# x16-to-mxm3.net
KiCad netlist of a schematic drawn in EAGLE
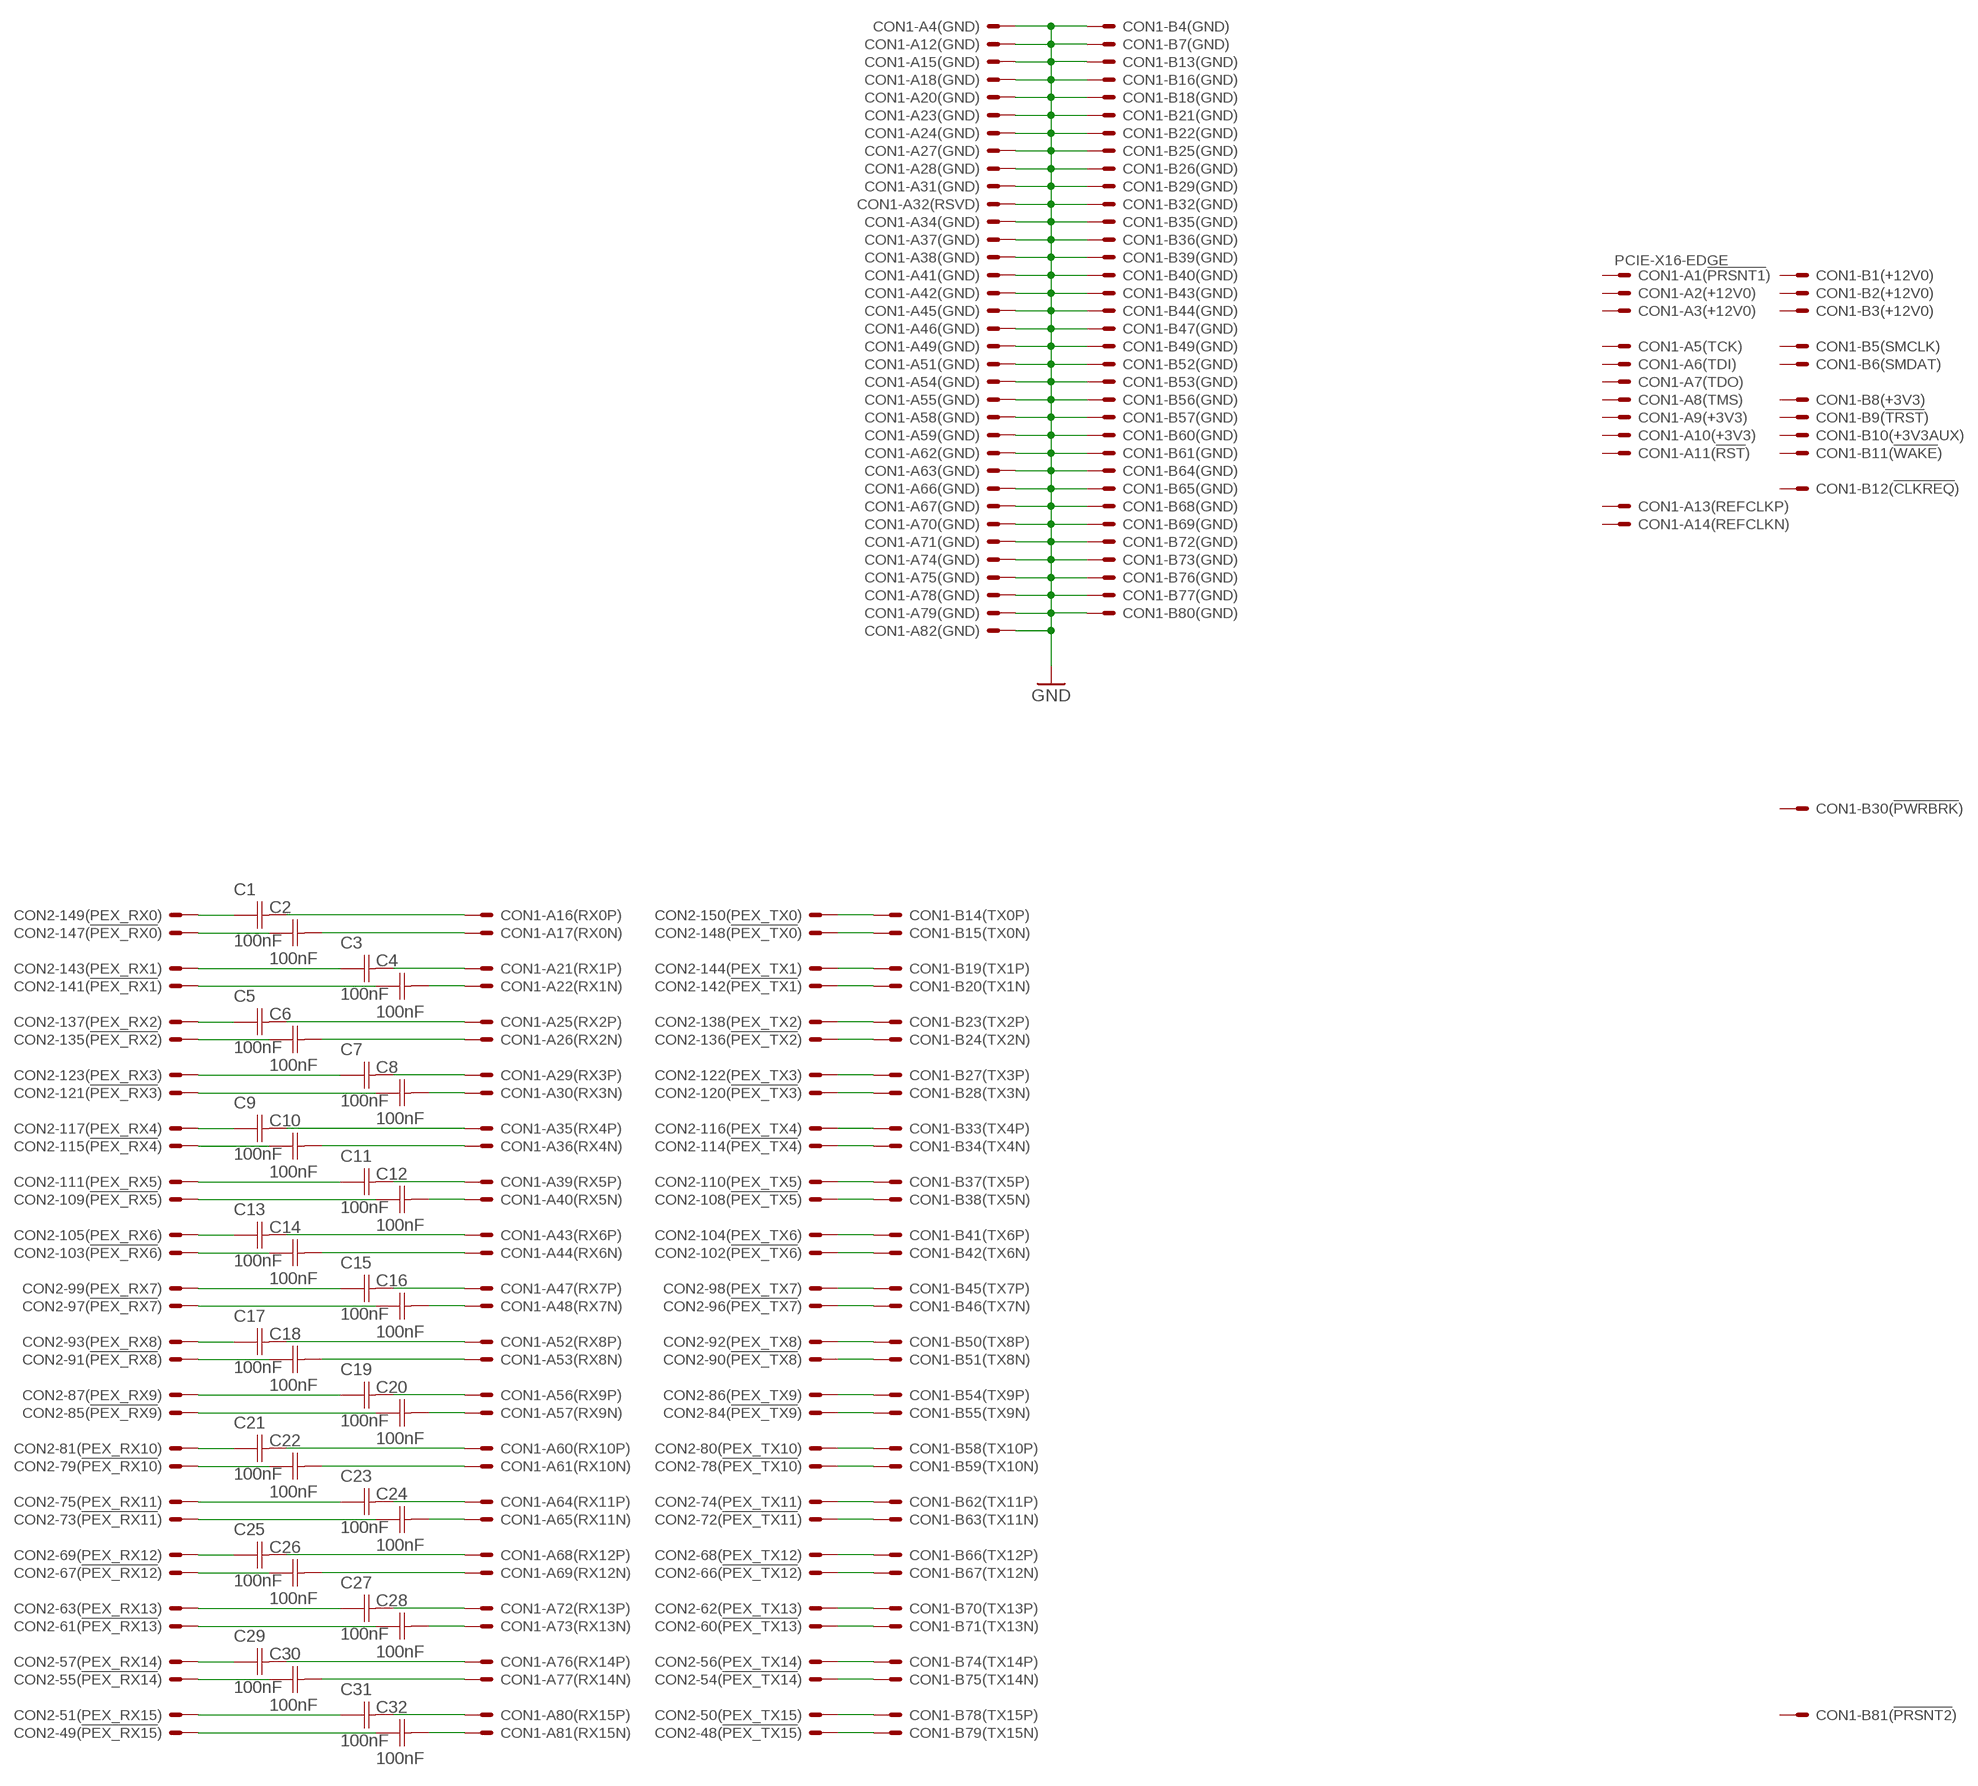
[diagram p0: schematic, sheet 1, part 1 of 2]
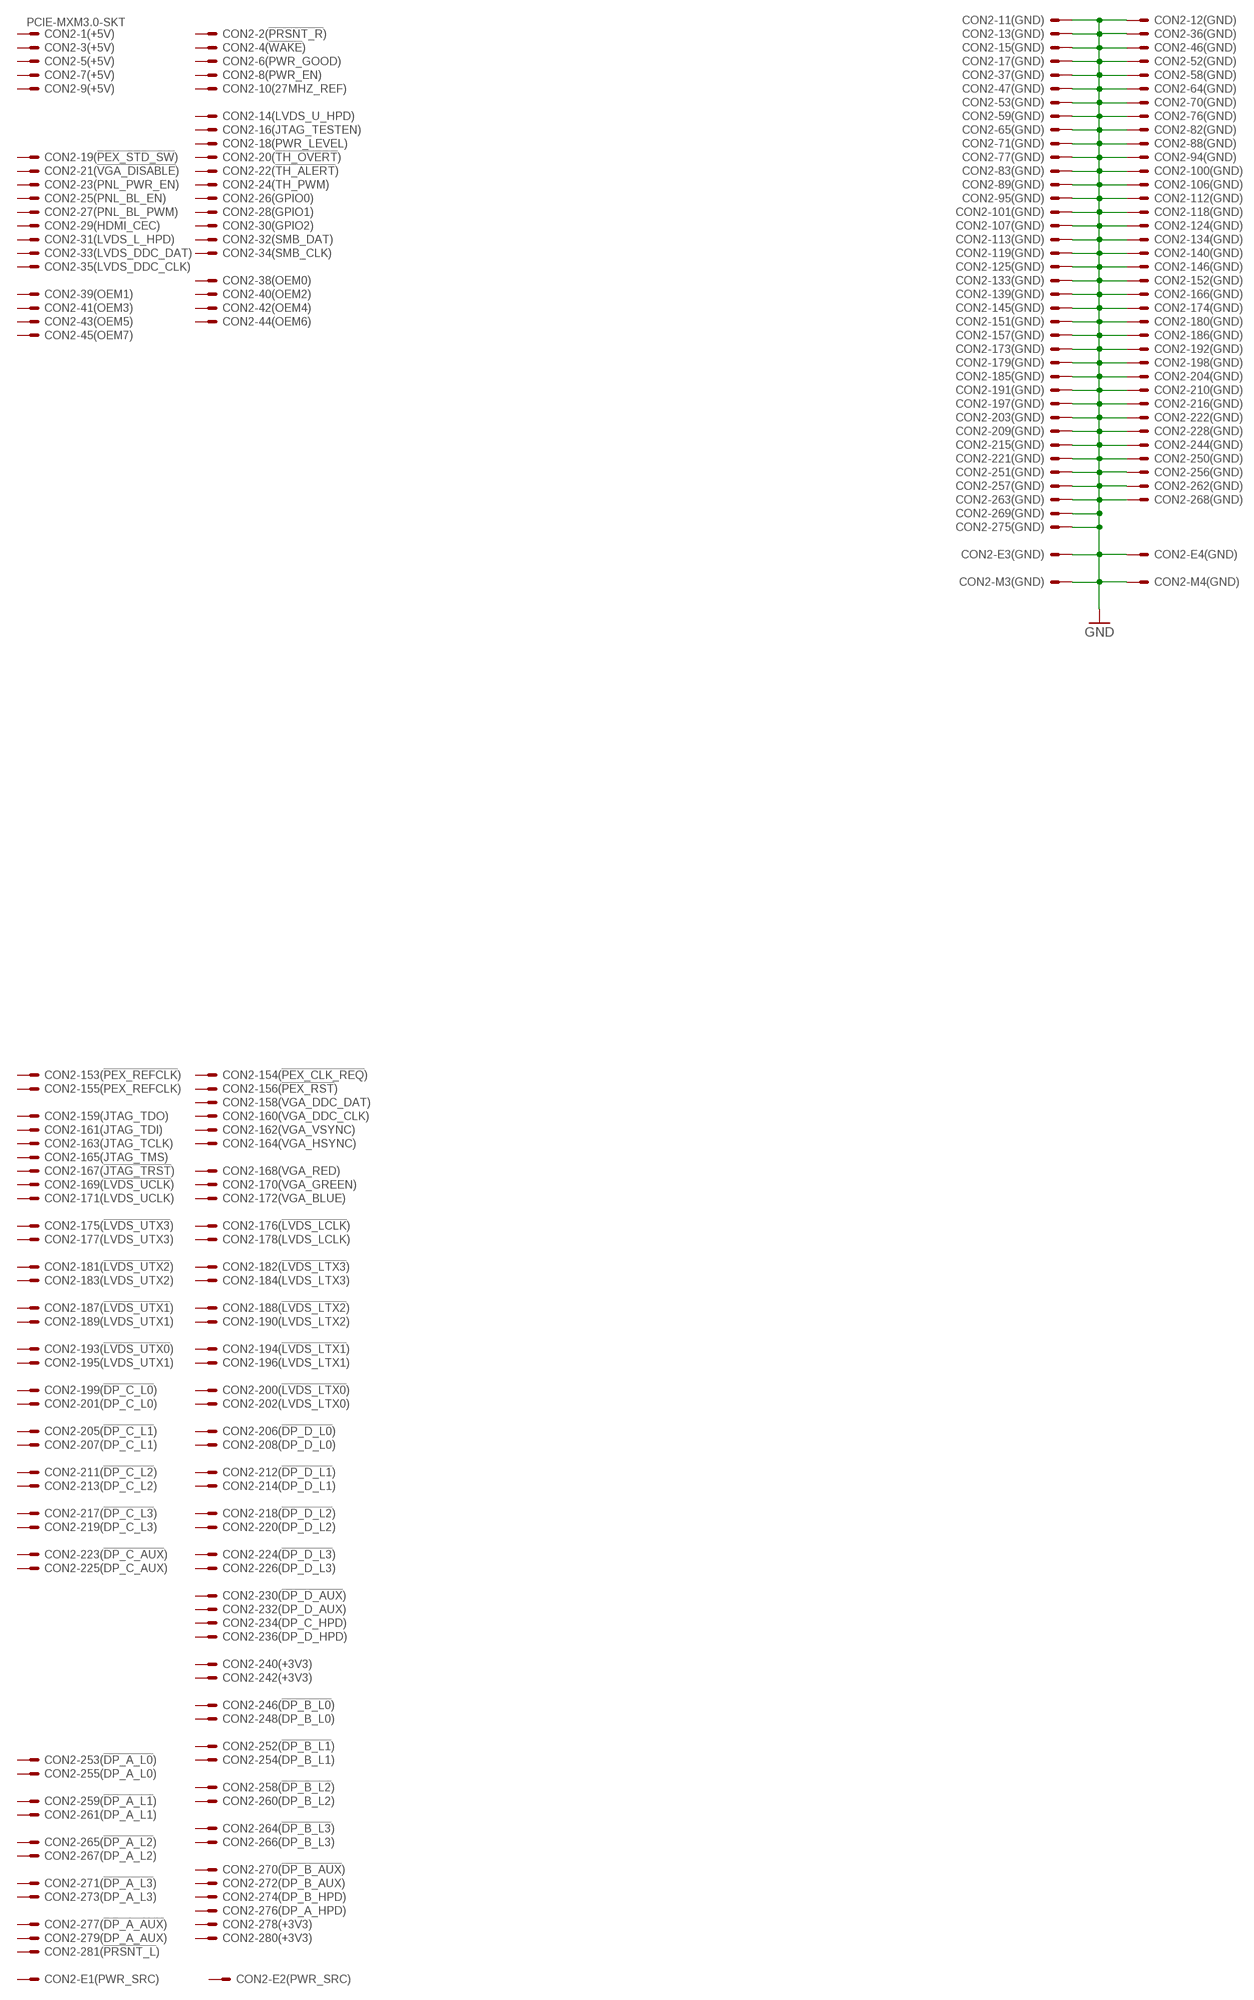
[diagram p1: schematic, sheet 1, part 2 of 2]

(export (version "E")
  (design (tool "Eeschema 10.0.6"))
  (components
    (comp (ref "C1")
      (value "100nF")
      (footprint "eagle-import:CAP0402")
      (libsource (lib "eagle-import") (part "CAPACITOR-0402"))
    )
    (comp (ref "C2")
      (value "100nF")
      (footprint "eagle-import:CAP0402")
      (libsource (lib "eagle-import") (part "CAPACITOR-0402"))
    )
    (comp (ref "C3")
      (value "100nF")
      (footprint "eagle-import:CAP0402")
      (libsource (lib "eagle-import") (part "CAPACITOR-0402"))
    )
    (comp (ref "C4")
      (value "100nF")
      (footprint "eagle-import:CAP0402")
      (libsource (lib "eagle-import") (part "CAPACITOR-0402"))
    )
    (comp (ref "C5")
      (value "100nF")
      (footprint "eagle-import:CAP0402")
      (libsource (lib "eagle-import") (part "CAPACITOR-0402"))
    )
    (comp (ref "C6")
      (value "100nF")
      (footprint "eagle-import:CAP0402")
      (libsource (lib "eagle-import") (part "CAPACITOR-0402"))
    )
    (comp (ref "C7")
      (value "100nF")
      (footprint "eagle-import:CAP0402")
      (libsource (lib "eagle-import") (part "CAPACITOR-0402"))
    )
    (comp (ref "C8")
      (value "100nF")
      (footprint "eagle-import:CAP0402")
      (libsource (lib "eagle-import") (part "CAPACITOR-0402"))
    )
    (comp (ref "C9")
      (value "100nF")
      (footprint "eagle-import:CAP0402")
      (libsource (lib "eagle-import") (part "CAPACITOR-0402"))
    )
    (comp (ref "C10")
      (value "100nF")
      (footprint "eagle-import:CAP0402")
      (libsource (lib "eagle-import") (part "CAPACITOR-0402"))
    )
    (comp (ref "C11")
      (value "100nF")
      (footprint "eagle-import:CAP0402")
      (libsource (lib "eagle-import") (part "CAPACITOR-0402"))
    )
    (comp (ref "C12")
      (value "100nF")
      (footprint "eagle-import:CAP0402")
      (libsource (lib "eagle-import") (part "CAPACITOR-0402"))
    )
    (comp (ref "C13")
      (value "100nF")
      (footprint "eagle-import:CAP0402")
      (libsource (lib "eagle-import") (part "CAPACITOR-0402"))
    )
    (comp (ref "C14")
      (value "100nF")
      (footprint "eagle-import:CAP0402")
      (libsource (lib "eagle-import") (part "CAPACITOR-0402"))
    )
    (comp (ref "C15")
      (value "100nF")
      (footprint "eagle-import:CAP0402")
      (libsource (lib "eagle-import") (part "CAPACITOR-0402"))
    )
    (comp (ref "C16")
      (value "100nF")
      (footprint "eagle-import:CAP0402")
      (libsource (lib "eagle-import") (part "CAPACITOR-0402"))
    )
    (comp (ref "C17")
      (value "100nF")
      (footprint "eagle-import:CAP0402")
      (libsource (lib "eagle-import") (part "CAPACITOR-0402"))
    )
    (comp (ref "C18")
      (value "100nF")
      (footprint "eagle-import:CAP0402")
      (libsource (lib "eagle-import") (part "CAPACITOR-0402"))
    )
    (comp (ref "C19")
      (value "100nF")
      (footprint "eagle-import:CAP0402")
      (libsource (lib "eagle-import") (part "CAPACITOR-0402"))
    )
    (comp (ref "C20")
      (value "100nF")
      (footprint "eagle-import:CAP0402")
      (libsource (lib "eagle-import") (part "CAPACITOR-0402"))
    )
    (comp (ref "C21")
      (value "100nF")
      (footprint "eagle-import:CAP0402")
      (libsource (lib "eagle-import") (part "CAPACITOR-0402"))
    )
    (comp (ref "C22")
      (value "100nF")
      (footprint "eagle-import:CAP0402")
      (libsource (lib "eagle-import") (part "CAPACITOR-0402"))
    )
    (comp (ref "C23")
      (value "100nF")
      (footprint "eagle-import:CAP0402")
      (libsource (lib "eagle-import") (part "CAPACITOR-0402"))
    )
    (comp (ref "C24")
      (value "100nF")
      (footprint "eagle-import:CAP0402")
      (libsource (lib "eagle-import") (part "CAPACITOR-0402"))
    )
    (comp (ref "C25")
      (value "100nF")
      (footprint "eagle-import:CAP0402")
      (libsource (lib "eagle-import") (part "CAPACITOR-0402"))
    )
    (comp (ref "C26")
      (value "100nF")
      (footprint "eagle-import:CAP0402")
      (libsource (lib "eagle-import") (part "CAPACITOR-0402"))
    )
    (comp (ref "C27")
      (value "100nF")
      (footprint "eagle-import:CAP0402")
      (libsource (lib "eagle-import") (part "CAPACITOR-0402"))
    )
    (comp (ref "C28")
      (value "100nF")
      (footprint "eagle-import:CAP0402")
      (libsource (lib "eagle-import") (part "CAPACITOR-0402"))
    )
    (comp (ref "C29")
      (value "100nF")
      (footprint "eagle-import:CAP0402")
      (libsource (lib "eagle-import") (part "CAPACITOR-0402"))
    )
    (comp (ref "C30")
      (value "100nF")
      (footprint "eagle-import:CAP0402")
      (libsource (lib "eagle-import") (part "CAPACITOR-0402"))
    )
    (comp (ref "C31")
      (value "100nF")
      (footprint "eagle-import:CAP0402")
      (libsource (lib "eagle-import") (part "CAPACITOR-0402"))
    )
    (comp (ref "C32")
      (value "100nF")
      (footprint "eagle-import:CAP0402")
      (libsource (lib "eagle-import") (part "CAPACITOR-0402"))
    )
    (comp (ref "CON1")
      (value "PCIE-X16-EDGE")
      (footprint "eagle-import:PCIE-X16-EDGE")
      (libsource (lib "eagle-import") (part "PCIE-X16-EDGE"))
    )
    (comp (ref "CON2")
      (value "PCIE-MXM3.0-SKT")
      (footprint "eagle-import:PCIE-MXM3.0-SKT")
      (libsource (lib "eagle-import") (part "PCIE-MXM3.0-SKT"))
    )
  )
  (nets
    (net (code "1") (name "GND") (class "Default")
      (node (ref "CON1") (pin "A12") (pinfunction "S_A12") (pintype "passive"))
      (node (ref "CON1") (pin "A15") (pinfunction "S_A15") (pintype "passive"))
      (node (ref "CON1") (pin "A18") (pinfunction "S_A18") (pintype "passive"))
      (node (ref "CON1") (pin "A20") (pinfunction "S_A20") (pintype "passive"))
      (node (ref "CON1") (pin "A23") (pinfunction "S_A23") (pintype "passive"))
      (node (ref "CON1") (pin "A24") (pinfunction "S_A24") (pintype "passive"))
      (node (ref "CON1") (pin "A27") (pinfunction "S_A27") (pintype "passive"))
      (node (ref "CON1") (pin "A28") (pinfunction "S_A28") (pintype "passive"))
      (node (ref "CON1") (pin "A31") (pinfunction "S_A31") (pintype "passive"))
      (node (ref "CON1") (pin "A32") (pinfunction "S_A32") (pintype "passive"))
      (node (ref "CON1") (pin "A34") (pinfunction "S_A34") (pintype "passive"))
      (node (ref "CON1") (pin "A37") (pinfunction "S_A37") (pintype "passive"))
      (node (ref "CON1") (pin "A38") (pinfunction "S_A38") (pintype "passive"))
      (node (ref "CON1") (pin "A4") (pinfunction "S_A4") (pintype "passive"))
      (node (ref "CON1") (pin "A41") (pinfunction "S_A41") (pintype "passive"))
      (node (ref "CON1") (pin "A42") (pinfunction "S_A42") (pintype "passive"))
      (node (ref "CON1") (pin "A45") (pinfunction "S_A45") (pintype "passive"))
      (node (ref "CON1") (pin "A46") (pinfunction "S_A46") (pintype "passive"))
      (node (ref "CON1") (pin "A49") (pinfunction "S_A49") (pintype "passive"))
      (node (ref "CON1") (pin "A51") (pinfunction "S_A51") (pintype "passive"))
      (node (ref "CON1") (pin "A54") (pinfunction "S_A54") (pintype "passive"))
      (node (ref "CON1") (pin "A55") (pinfunction "S_A55") (pintype "passive"))
      (node (ref "CON1") (pin "A58") (pinfunction "S_A58") (pintype "passive"))
      (node (ref "CON1") (pin "A59") (pinfunction "S_A59") (pintype "passive"))
      (node (ref "CON1") (pin "A62") (pinfunction "S_A62") (pintype "passive"))
      (node (ref "CON1") (pin "A63") (pinfunction "S_A63") (pintype "passive"))
      (node (ref "CON1") (pin "A66") (pinfunction "S_A66") (pintype "passive"))
      (node (ref "CON1") (pin "A67") (pinfunction "S_A67") (pintype "passive"))
      (node (ref "CON1") (pin "A70") (pinfunction "S_A70") (pintype "passive"))
      (node (ref "CON1") (pin "A71") (pinfunction "S_A71") (pintype "passive"))
      (node (ref "CON1") (pin "A74") (pinfunction "S_A74") (pintype "passive"))
      (node (ref "CON1") (pin "A75") (pinfunction "S_A75") (pintype "passive"))
      (node (ref "CON1") (pin "A78") (pinfunction "S_A78") (pintype "passive"))
      (node (ref "CON1") (pin "A79") (pinfunction "S_A79") (pintype "passive"))
      (node (ref "CON1") (pin "A82") (pinfunction "S_A82") (pintype "passive"))
      (node (ref "CON1") (pin "B13") (pinfunction "S_B13") (pintype "passive"))
      (node (ref "CON1") (pin "B16") (pinfunction "S_B16") (pintype "passive"))
      (node (ref "CON1") (pin "B18") (pinfunction "S_B18") (pintype "passive"))
      (node (ref "CON1") (pin "B21") (pinfunction "S_B21") (pintype "passive"))
      (node (ref "CON1") (pin "B22") (pinfunction "S_B22") (pintype "passive"))
      (node (ref "CON1") (pin "B25") (pinfunction "S_B25") (pintype "passive"))
      (node (ref "CON1") (pin "B26") (pinfunction "S_B26") (pintype "passive"))
      (node (ref "CON1") (pin "B29") (pinfunction "S_B29") (pintype "passive"))
      (node (ref "CON1") (pin "B32") (pinfunction "S_B32") (pintype "passive"))
      (node (ref "CON1") (pin "B35") (pinfunction "S_B35") (pintype "passive"))
      (node (ref "CON1") (pin "B36") (pinfunction "S_B36") (pintype "passive"))
      (node (ref "CON1") (pin "B39") (pinfunction "S_B39") (pintype "passive"))
      (node (ref "CON1") (pin "B4") (pinfunction "S_B4") (pintype "passive"))
      (node (ref "CON1") (pin "B40") (pinfunction "S_B40") (pintype "passive"))
      (node (ref "CON1") (pin "B43") (pinfunction "S_B43") (pintype "passive"))
      (node (ref "CON1") (pin "B44") (pinfunction "S_B44") (pintype "passive"))
      (node (ref "CON1") (pin "B47") (pinfunction "S_B47") (pintype "passive"))
      (node (ref "CON1") (pin "B49") (pinfunction "S_B49") (pintype "passive"))
      (node (ref "CON1") (pin "B52") (pinfunction "S_B52") (pintype "passive"))
      (node (ref "CON1") (pin "B53") (pinfunction "S_B53") (pintype "passive"))
      (node (ref "CON1") (pin "B56") (pinfunction "S_B56") (pintype "passive"))
      (node (ref "CON1") (pin "B57") (pinfunction "S_B57") (pintype "passive"))
      (node (ref "CON1") (pin "B60") (pinfunction "S_B60") (pintype "passive"))
      (node (ref "CON1") (pin "B61") (pinfunction "S_B61") (pintype "passive"))
      (node (ref "CON1") (pin "B64") (pinfunction "S_B64") (pintype "passive"))
      (node (ref "CON1") (pin "B65") (pinfunction "S_B65") (pintype "passive"))
      (node (ref "CON1") (pin "B68") (pinfunction "S_B68") (pintype "passive"))
      (node (ref "CON1") (pin "B69") (pinfunction "S_B69") (pintype "passive"))
      (node (ref "CON1") (pin "B7") (pinfunction "S_B7") (pintype "passive"))
      (node (ref "CON1") (pin "B72") (pinfunction "S_B72") (pintype "passive"))
      (node (ref "CON1") (pin "B73") (pinfunction "S_B73") (pintype "passive"))
      (node (ref "CON1") (pin "B76") (pinfunction "S_B76") (pintype "passive"))
      (node (ref "CON1") (pin "B77") (pinfunction "S_B77") (pintype "passive"))
      (node (ref "CON1") (pin "B80") (pinfunction "S_B80") (pintype "passive"))
      (node (ref "CON2") (pin "100") (pinfunction "S_100") (pintype "passive"))
      (node (ref "CON2") (pin "101") (pinfunction "S_101") (pintype "passive"))
      (node (ref "CON2") (pin "106") (pinfunction "S_106") (pintype "passive"))
      (node (ref "CON2") (pin "107") (pinfunction "S_107") (pintype "passive"))
      (node (ref "CON2") (pin "11") (pinfunction "S_11") (pintype "passive"))
      (node (ref "CON2") (pin "112") (pinfunction "S_112") (pintype "passive"))
      (node (ref "CON2") (pin "113") (pinfunction "S_113") (pintype "passive"))
      (node (ref "CON2") (pin "118") (pinfunction "S_118") (pintype "passive"))
      (node (ref "CON2") (pin "119") (pinfunction "S_119") (pintype "passive"))
      (node (ref "CON2") (pin "12") (pinfunction "S_12") (pintype "passive"))
      (node (ref "CON2") (pin "124") (pinfunction "S_124") (pintype "passive"))
      (node (ref "CON2") (pin "125") (pinfunction "S_125") (pintype "passive"))
      (node (ref "CON2") (pin "13") (pinfunction "S_13") (pintype "passive"))
      (node (ref "CON2") (pin "133") (pinfunction "S_133") (pintype "passive"))
      (node (ref "CON2") (pin "134") (pinfunction "S_134") (pintype "passive"))
      (node (ref "CON2") (pin "139") (pinfunction "S_139") (pintype "passive"))
      (node (ref "CON2") (pin "140") (pinfunction "S_140") (pintype "passive"))
      (node (ref "CON2") (pin "145") (pinfunction "S_145") (pintype "passive"))
      (node (ref "CON2") (pin "146") (pinfunction "S_146") (pintype "passive"))
      (node (ref "CON2") (pin "15") (pinfunction "S_15") (pintype "passive"))
      (node (ref "CON2") (pin "151") (pinfunction "S_151") (pintype "passive"))
      (node (ref "CON2") (pin "152") (pinfunction "S_152") (pintype "passive"))
      (node (ref "CON2") (pin "157") (pinfunction "S_157") (pintype "passive"))
      (node (ref "CON2") (pin "166") (pinfunction "S_166") (pintype "passive"))
      (node (ref "CON2") (pin "17") (pinfunction "S_17") (pintype "passive"))
      (node (ref "CON2") (pin "173") (pinfunction "S_173") (pintype "passive"))
      (node (ref "CON2") (pin "174") (pinfunction "S_174") (pintype "passive"))
      (node (ref "CON2") (pin "179") (pinfunction "S_179") (pintype "passive"))
      (node (ref "CON2") (pin "180") (pinfunction "S_180") (pintype "passive"))
      (node (ref "CON2") (pin "185") (pinfunction "S_185") (pintype "passive"))
      (node (ref "CON2") (pin "186") (pinfunction "S_186") (pintype "passive"))
      (node (ref "CON2") (pin "191") (pinfunction "S_191") (pintype "passive"))
      (node (ref "CON2") (pin "192") (pinfunction "S_192") (pintype "passive"))
      (node (ref "CON2") (pin "197") (pinfunction "S_197") (pintype "passive"))
      (node (ref "CON2") (pin "198") (pinfunction "S_198") (pintype "passive"))
      (node (ref "CON2") (pin "203") (pinfunction "S_203") (pintype "passive"))
      (node (ref "CON2") (pin "204") (pinfunction "S_204") (pintype "passive"))
      (node (ref "CON2") (pin "209") (pinfunction "S_209") (pintype "passive"))
      (node (ref "CON2") (pin "210") (pinfunction "S_210") (pintype "passive"))
      (node (ref "CON2") (pin "215") (pinfunction "S_215") (pintype "passive"))
      (node (ref "CON2") (pin "216") (pinfunction "S_216") (pintype "passive"))
      (node (ref "CON2") (pin "221") (pinfunction "S_221") (pintype "passive"))
      (node (ref "CON2") (pin "222") (pinfunction "S_222") (pintype "passive"))
      (node (ref "CON2") (pin "228") (pinfunction "S_228") (pintype "passive"))
      (node (ref "CON2") (pin "244") (pinfunction "S_244") (pintype "passive"))
      (node (ref "CON2") (pin "250") (pinfunction "S_250") (pintype "passive"))
      (node (ref "CON2") (pin "251") (pinfunction "S_251") (pintype "passive"))
      (node (ref "CON2") (pin "256") (pinfunction "S_256") (pintype "passive"))
      (node (ref "CON2") (pin "257") (pinfunction "S_257") (pintype "passive"))
      (node (ref "CON2") (pin "262") (pinfunction "S_262") (pintype "passive"))
      (node (ref "CON2") (pin "263") (pinfunction "S_263") (pintype "passive"))
      (node (ref "CON2") (pin "268") (pinfunction "S_268") (pintype "passive"))
      (node (ref "CON2") (pin "269") (pinfunction "S_269") (pintype "passive"))
      (node (ref "CON2") (pin "275") (pinfunction "S_275") (pintype "passive"))
      (node (ref "CON2") (pin "36") (pinfunction "S_36") (pintype "passive"))
      (node (ref "CON2") (pin "37") (pinfunction "S_37") (pintype "passive"))
      (node (ref "CON2") (pin "46") (pinfunction "S_46") (pintype "passive"))
      (node (ref "CON2") (pin "47") (pinfunction "S_47") (pintype "passive"))
      (node (ref "CON2") (pin "52") (pinfunction "S_52") (pintype "passive"))
      (node (ref "CON2") (pin "53") (pinfunction "S_53") (pintype "passive"))
      (node (ref "CON2") (pin "58") (pinfunction "S_58") (pintype "passive"))
      (node (ref "CON2") (pin "59") (pinfunction "S_59") (pintype "passive"))
      (node (ref "CON2") (pin "64") (pinfunction "S_64") (pintype "passive"))
      (node (ref "CON2") (pin "65") (pinfunction "S_65") (pintype "passive"))
      (node (ref "CON2") (pin "70") (pinfunction "S_70") (pintype "passive"))
      (node (ref "CON2") (pin "71") (pinfunction "S_71") (pintype "passive"))
      (node (ref "CON2") (pin "76") (pinfunction "S_76") (pintype "passive"))
      (node (ref "CON2") (pin "77") (pinfunction "S_77") (pintype "passive"))
      (node (ref "CON2") (pin "82") (pinfunction "S_82") (pintype "passive"))
      (node (ref "CON2") (pin "83") (pinfunction "S_83") (pintype "passive"))
      (node (ref "CON2") (pin "88") (pinfunction "S_88") (pintype "passive"))
      (node (ref "CON2") (pin "89") (pinfunction "S_89") (pintype "passive"))
      (node (ref "CON2") (pin "94") (pinfunction "S_94") (pintype "passive"))
      (node (ref "CON2") (pin "95") (pinfunction "S_95") (pintype "passive"))
      (node (ref "CON2") (pin "E3") (pinfunction "S_E3") (pintype "passive"))
      (node (ref "CON2") (pin "E4") (pinfunction "S_E4") (pintype "passive"))
      (node (ref "CON2") (pin "M3") (pinfunction "S_M3") (pintype "passive"))
      (node (ref "CON2") (pin "M4") (pinfunction "S_M4") (pintype "passive"))
    )
    (net (code "2") (name "Net-(C1-C1)") (class "Default")
      (node (ref "C1") (pin "1") (pinfunction "C1_1") (pintype "passive"))
      (node (ref "CON2") (pin "149") (pinfunction "S_149") (pintype "passive"))
    )
    (net (code "3") (name "Net-(C1-C2)") (class "Default")
      (node (ref "C1") (pin "2") (pinfunction "C2_2") (pintype "passive"))
      (node (ref "CON1") (pin "A16") (pinfunction "S_A16") (pintype "passive"))
    )
    (net (code "4") (name "Net-(C2-C1)") (class "Default")
      (node (ref "C2") (pin "1") (pinfunction "C1_1") (pintype "passive"))
      (node (ref "CON2") (pin "147") (pinfunction "S_147") (pintype "passive"))
    )
    (net (code "5") (name "Net-(C2-C2)") (class "Default")
      (node (ref "C2") (pin "2") (pinfunction "C2_2") (pintype "passive"))
      (node (ref "CON1") (pin "A17") (pinfunction "S_A17") (pintype "passive"))
    )
    (net (code "6") (name "Net-(C3-C1)") (class "Default")
      (node (ref "C3") (pin "1") (pinfunction "C1_1") (pintype "passive"))
      (node (ref "CON2") (pin "143") (pinfunction "S_143") (pintype "passive"))
    )
    (net (code "7") (name "Net-(C3-C2)") (class "Default")
      (node (ref "C3") (pin "2") (pinfunction "C2_2") (pintype "passive"))
      (node (ref "CON1") (pin "A21") (pinfunction "S_A21") (pintype "passive"))
    )
    (net (code "8") (name "Net-(C4-C1)") (class "Default")
      (node (ref "C4") (pin "1") (pinfunction "C1_1") (pintype "passive"))
      (node (ref "CON2") (pin "141") (pinfunction "S_141") (pintype "passive"))
    )
    (net (code "9") (name "Net-(C4-C2)") (class "Default")
      (node (ref "C4") (pin "2") (pinfunction "C2_2") (pintype "passive"))
      (node (ref "CON1") (pin "A22") (pinfunction "S_A22") (pintype "passive"))
    )
    (net (code "10") (name "Net-(C5-C1)") (class "Default")
      (node (ref "C5") (pin "1") (pinfunction "C1_1") (pintype "passive"))
      (node (ref "CON2") (pin "137") (pinfunction "S_137") (pintype "passive"))
    )
    (net (code "11") (name "Net-(C5-C2)") (class "Default")
      (node (ref "C5") (pin "2") (pinfunction "C2_2") (pintype "passive"))
      (node (ref "CON1") (pin "A25") (pinfunction "S_A25") (pintype "passive"))
    )
    (net (code "12") (name "Net-(C6-C1)") (class "Default")
      (node (ref "C6") (pin "1") (pinfunction "C1_1") (pintype "passive"))
      (node (ref "CON2") (pin "135") (pinfunction "S_135") (pintype "passive"))
    )
    (net (code "13") (name "Net-(C6-C2)") (class "Default")
      (node (ref "C6") (pin "2") (pinfunction "C2_2") (pintype "passive"))
      (node (ref "CON1") (pin "A26") (pinfunction "S_A26") (pintype "passive"))
    )
    (net (code "14") (name "Net-(C7-C1)") (class "Default")
      (node (ref "C7") (pin "1") (pinfunction "C1_1") (pintype "passive"))
      (node (ref "CON2") (pin "123") (pinfunction "S_123") (pintype "passive"))
    )
    (net (code "15") (name "Net-(C7-C2)") (class "Default")
      (node (ref "C7") (pin "2") (pinfunction "C2_2") (pintype "passive"))
      (node (ref "CON1") (pin "A29") (pinfunction "S_A29") (pintype "passive"))
    )
    (net (code "16") (name "Net-(C8-C1)") (class "Default")
      (node (ref "C8") (pin "1") (pinfunction "C1_1") (pintype "passive"))
      (node (ref "CON2") (pin "121") (pinfunction "S_121") (pintype "passive"))
    )
    (net (code "17") (name "Net-(C8-C2)") (class "Default")
      (node (ref "C8") (pin "2") (pinfunction "C2_2") (pintype "passive"))
      (node (ref "CON1") (pin "A30") (pinfunction "S_A30") (pintype "passive"))
    )
    (net (code "18") (name "Net-(C9-C1)") (class "Default")
      (node (ref "C9") (pin "1") (pinfunction "C1_1") (pintype "passive"))
      (node (ref "CON2") (pin "117") (pinfunction "S_117") (pintype "passive"))
    )
    (net (code "19") (name "Net-(C9-C2)") (class "Default")
      (node (ref "C9") (pin "2") (pinfunction "C2_2") (pintype "passive"))
      (node (ref "CON1") (pin "A35") (pinfunction "S_A35") (pintype "passive"))
    )
    (net (code "20") (name "Net-(C10-C1)") (class "Default")
      (node (ref "C10") (pin "1") (pinfunction "C1_1") (pintype "passive"))
      (node (ref "CON2") (pin "115") (pinfunction "S_115") (pintype "passive"))
    )
    (net (code "21") (name "Net-(C10-C2)") (class "Default")
      (node (ref "C10") (pin "2") (pinfunction "C2_2") (pintype "passive"))
      (node (ref "CON1") (pin "A36") (pinfunction "S_A36") (pintype "passive"))
    )
    (net (code "22") (name "Net-(C11-C1)") (class "Default")
      (node (ref "C11") (pin "1") (pinfunction "C1_1") (pintype "passive"))
      (node (ref "CON2") (pin "111") (pinfunction "S_111") (pintype "passive"))
    )
    (net (code "23") (name "Net-(C11-C2)") (class "Default")
      (node (ref "C11") (pin "2") (pinfunction "C2_2") (pintype "passive"))
      (node (ref "CON1") (pin "A39") (pinfunction "S_A39") (pintype "passive"))
    )
    (net (code "24") (name "Net-(C12-C1)") (class "Default")
      (node (ref "C12") (pin "1") (pinfunction "C1_1") (pintype "passive"))
      (node (ref "CON2") (pin "109") (pinfunction "S_109") (pintype "passive"))
    )
    (net (code "25") (name "Net-(C12-C2)") (class "Default")
      (node (ref "C12") (pin "2") (pinfunction "C2_2") (pintype "passive"))
      (node (ref "CON1") (pin "A40") (pinfunction "S_A40") (pintype "passive"))
    )
    (net (code "26") (name "Net-(C13-C1)") (class "Default")
      (node (ref "C13") (pin "1") (pinfunction "C1_1") (pintype "passive"))
      (node (ref "CON2") (pin "105") (pinfunction "S_105") (pintype "passive"))
    )
    (net (code "27") (name "Net-(C13-C2)") (class "Default")
      (node (ref "C13") (pin "2") (pinfunction "C2_2") (pintype "passive"))
      (node (ref "CON1") (pin "A43") (pinfunction "S_A43") (pintype "passive"))
    )
    (net (code "28") (name "Net-(C14-C1)") (class "Default")
      (node (ref "C14") (pin "1") (pinfunction "C1_1") (pintype "passive"))
      (node (ref "CON2") (pin "103") (pinfunction "S_103") (pintype "passive"))
    )
    (net (code "29") (name "Net-(C14-C2)") (class "Default")
      (node (ref "C14") (pin "2") (pinfunction "C2_2") (pintype "passive"))
      (node (ref "CON1") (pin "A44") (pinfunction "S_A44") (pintype "passive"))
    )
    (net (code "30") (name "Net-(C15-C1)") (class "Default")
      (node (ref "C15") (pin "1") (pinfunction "C1_1") (pintype "passive"))
      (node (ref "CON2") (pin "99") (pinfunction "S_99") (pintype "passive"))
    )
    (net (code "31") (name "Net-(C15-C2)") (class "Default")
      (node (ref "C15") (pin "2") (pinfunction "C2_2") (pintype "passive"))
      (node (ref "CON1") (pin "A47") (pinfunction "S_A47") (pintype "passive"))
    )
    (net (code "32") (name "Net-(C16-C1)") (class "Default")
      (node (ref "C16") (pin "1") (pinfunction "C1_1") (pintype "passive"))
      (node (ref "CON2") (pin "97") (pinfunction "S_97") (pintype "passive"))
    )
    (net (code "33") (name "Net-(C16-C2)") (class "Default")
      (node (ref "C16") (pin "2") (pinfunction "C2_2") (pintype "passive"))
      (node (ref "CON1") (pin "A48") (pinfunction "S_A48") (pintype "passive"))
    )
    (net (code "34") (name "Net-(C17-C1)") (class "Default")
      (node (ref "C17") (pin "1") (pinfunction "C1_1") (pintype "passive"))
      (node (ref "CON2") (pin "93") (pinfunction "S_93") (pintype "passive"))
    )
    (net (code "35") (name "Net-(C17-C2)") (class "Default")
      (node (ref "C17") (pin "2") (pinfunction "C2_2") (pintype "passive"))
      (node (ref "CON1") (pin "A52") (pinfunction "S_A52") (pintype "passive"))
    )
    (net (code "36") (name "Net-(C18-C1)") (class "Default")
      (node (ref "C18") (pin "1") (pinfunction "C1_1") (pintype "passive"))
      (node (ref "CON2") (pin "91") (pinfunction "S_91") (pintype "passive"))
    )
    (net (code "37") (name "Net-(C18-C2)") (class "Default")
      (node (ref "C18") (pin "2") (pinfunction "C2_2") (pintype "passive"))
      (node (ref "CON1") (pin "A53") (pinfunction "S_A53") (pintype "passive"))
    )
    (net (code "38") (name "Net-(C19-C1)") (class "Default")
      (node (ref "C19") (pin "1") (pinfunction "C1_1") (pintype "passive"))
      (node (ref "CON2") (pin "87") (pinfunction "S_87") (pintype "passive"))
    )
    (net (code "39") (name "Net-(C19-C2)") (class "Default")
      (node (ref "C19") (pin "2") (pinfunction "C2_2") (pintype "passive"))
      (node (ref "CON1") (pin "A56") (pinfunction "S_A56") (pintype "passive"))
    )
    (net (code "40") (name "Net-(C20-C1)") (class "Default")
      (node (ref "C20") (pin "1") (pinfunction "C1_1") (pintype "passive"))
      (node (ref "CON2") (pin "85") (pinfunction "S_85") (pintype "passive"))
    )
    (net (code "41") (name "Net-(C20-C2)") (class "Default")
      (node (ref "C20") (pin "2") (pinfunction "C2_2") (pintype "passive"))
      (node (ref "CON1") (pin "A57") (pinfunction "S_A57") (pintype "passive"))
    )
    (net (code "42") (name "Net-(C21-C1)") (class "Default")
      (node (ref "C21") (pin "1") (pinfunction "C1_1") (pintype "passive"))
      (node (ref "CON2") (pin "81") (pinfunction "S_81") (pintype "passive"))
    )
    (net (code "43") (name "Net-(C21-C2)") (class "Default")
      (node (ref "C21") (pin "2") (pinfunction "C2_2") (pintype "passive"))
      (node (ref "CON1") (pin "A60") (pinfunction "S_A60") (pintype "passive"))
    )
    (net (code "44") (name "Net-(C22-C1)") (class "Default")
      (node (ref "C22") (pin "1") (pinfunction "C1_1") (pintype "passive"))
      (node (ref "CON2") (pin "79") (pinfunction "S_79") (pintype "passive"))
    )
    (net (code "45") (name "Net-(C22-C2)") (class "Default")
      (node (ref "C22") (pin "2") (pinfunction "C2_2") (pintype "passive"))
      (node (ref "CON1") (pin "A61") (pinfunction "S_A61") (pintype "passive"))
    )
    (net (code "46") (name "Net-(C23-C1)") (class "Default")
      (node (ref "C23") (pin "1") (pinfunction "C1_1") (pintype "passive"))
      (node (ref "CON2") (pin "75") (pinfunction "S_75") (pintype "passive"))
    )
    (net (code "47") (name "Net-(C23-C2)") (class "Default")
      (node (ref "C23") (pin "2") (pinfunction "C2_2") (pintype "passive"))
      (node (ref "CON1") (pin "A64") (pinfunction "S_A64") (pintype "passive"))
    )
    (net (code "48") (name "Net-(C24-C1)") (class "Default")
      (node (ref "C24") (pin "1") (pinfunction "C1_1") (pintype "passive"))
      (node (ref "CON2") (pin "73") (pinfunction "S_73") (pintype "passive"))
    )
    (net (code "49") (name "Net-(C24-C2)") (class "Default")
      (node (ref "C24") (pin "2") (pinfunction "C2_2") (pintype "passive"))
      (node (ref "CON1") (pin "A65") (pinfunction "S_A65") (pintype "passive"))
    )
    (net (code "50") (name "Net-(C25-C1)") (class "Default")
      (node (ref "C25") (pin "1") (pinfunction "C1_1") (pintype "passive"))
      (node (ref "CON2") (pin "69") (pinfunction "S_69") (pintype "passive"))
    )
    (net (code "51") (name "Net-(C25-C2)") (class "Default")
      (node (ref "C25") (pin "2") (pinfunction "C2_2") (pintype "passive"))
      (node (ref "CON1") (pin "A68") (pinfunction "S_A68") (pintype "passive"))
    )
    (net (code "52") (name "Net-(C26-C1)") (class "Default")
      (node (ref "C26") (pin "1") (pinfunction "C1_1") (pintype "passive"))
      (node (ref "CON2") (pin "67") (pinfunction "S_67") (pintype "passive"))
    )
    (net (code "53") (name "Net-(C26-C2)") (class "Default")
      (node (ref "C26") (pin "2") (pinfunction "C2_2") (pintype "passive"))
      (node (ref "CON1") (pin "A69") (pinfunction "S_A69") (pintype "passive"))
    )
    (net (code "54") (name "Net-(C27-C1)") (class "Default")
      (node (ref "C27") (pin "1") (pinfunction "C1_1") (pintype "passive"))
      (node (ref "CON2") (pin "63") (pinfunction "S_63") (pintype "passive"))
    )
    (net (code "55") (name "Net-(C27-C2)") (class "Default")
      (node (ref "C27") (pin "2") (pinfunction "C2_2") (pintype "passive"))
      (node (ref "CON1") (pin "A72") (pinfunction "S_A72") (pintype "passive"))
    )
    (net (code "56") (name "Net-(C28-C1)") (class "Default")
      (node (ref "C28") (pin "1") (pinfunction "C1_1") (pintype "passive"))
      (node (ref "CON2") (pin "61") (pinfunction "S_61") (pintype "passive"))
    )
    (net (code "57") (name "Net-(C28-C2)") (class "Default")
      (node (ref "C28") (pin "2") (pinfunction "C2_2") (pintype "passive"))
      (node (ref "CON1") (pin "A73") (pinfunction "S_A73") (pintype "passive"))
    )
    (net (code "58") (name "Net-(C29-C1)") (class "Default")
      (node (ref "C29") (pin "1") (pinfunction "C1_1") (pintype "passive"))
      (node (ref "CON2") (pin "57") (pinfunction "S_57") (pintype "passive"))
    )
    (net (code "59") (name "Net-(C29-C2)") (class "Default")
      (node (ref "C29") (pin "2") (pinfunction "C2_2") (pintype "passive"))
      (node (ref "CON1") (pin "A76") (pinfunction "S_A76") (pintype "passive"))
    )
    (net (code "60") (name "Net-(C30-C1)") (class "Default")
      (node (ref "C30") (pin "1") (pinfunction "C1_1") (pintype "passive"))
      (node (ref "CON2") (pin "55") (pinfunction "S_55") (pintype "passive"))
    )
    (net (code "61") (name "Net-(C30-C2)") (class "Default")
      (node (ref "C30") (pin "2") (pinfunction "C2_2") (pintype "passive"))
      (node (ref "CON1") (pin "A77") (pinfunction "S_A77") (pintype "passive"))
    )
    (net (code "62") (name "Net-(C31-C1)") (class "Default")
      (node (ref "C31") (pin "1") (pinfunction "C1_1") (pintype "passive"))
      (node (ref "CON2") (pin "51") (pinfunction "S_51") (pintype "passive"))
    )
    (net (code "63") (name "Net-(C31-C2)") (class "Default")
      (node (ref "C31") (pin "2") (pinfunction "C2_2") (pintype "passive"))
      (node (ref "CON1") (pin "A80") (pinfunction "S_A80") (pintype "passive"))
    )
    (net (code "64") (name "Net-(C32-C1)") (class "Default")
      (node (ref "C32") (pin "1") (pinfunction "C1_1") (pintype "passive"))
      (node (ref "CON2") (pin "49") (pinfunction "S_49") (pintype "passive"))
    )
    (net (code "65") (name "Net-(C32-C2)") (class "Default")
      (node (ref "C32") (pin "2") (pinfunction "C2_2") (pintype "passive"))
      (node (ref "CON1") (pin "A81") (pinfunction "S_A81") (pintype "passive"))
    )
    (net (code "66") (name "Net-(CON1CJ-S)") (class "Default")
      (node (ref "CON1") (pin "B14") (pinfunction "S_B14") (pintype "passive"))
      (node (ref "CON2") (pin "150") (pinfunction "S_150") (pintype "passive"))
    )
    (net (code "67") (name "Net-(CON1CK-S)") (class "Default")
      (node (ref "CON1") (pin "B15") (pinfunction "S_B15") (pintype "passive"))
      (node (ref "CON2") (pin "148") (pinfunction "S_148") (pintype "passive"))
    )
    (net (code "68") (name "Net-(CON1CO-S)") (class "Default")
      (node (ref "CON1") (pin "B19") (pinfunction "S_B19") (pintype "passive"))
      (node (ref "CON2") (pin "144") (pinfunction "S_144") (pintype "passive"))
    )
    (net (code "69") (name "Net-(CON1CQ-S)") (class "Default")
      (node (ref "CON1") (pin "B20") (pinfunction "S_B20") (pintype "passive"))
      (node (ref "CON2") (pin "142") (pinfunction "S_142") (pintype "passive"))
    )
    (net (code "70") (name "Net-(CON1CT-S)") (class "Default")
      (node (ref "CON1") (pin "B23") (pinfunction "S_B23") (pintype "passive"))
      (node (ref "CON2") (pin "138") (pinfunction "S_138") (pintype "passive"))
    )
    (net (code "71") (name "Net-(CON1CU-S)") (class "Default")
      (node (ref "CON1") (pin "B24") (pinfunction "S_B24") (pintype "passive"))
      (node (ref "CON2") (pin "136") (pinfunction "S_136") (pintype "passive"))
    )
    (net (code "72") (name "Net-(CON1CX-S)") (class "Default")
      (node (ref "CON1") (pin "B27") (pinfunction "S_B27") (pintype "passive"))
      (node (ref "CON2") (pin "122") (pinfunction "S_122") (pintype "passive"))
    )
    (net (code "73") (name "Net-(CON1CY-S)") (class "Default")
      (node (ref "CON1") (pin "B28") (pinfunction "S_B28") (pintype "passive"))
      (node (ref "CON2") (pin "120") (pinfunction "S_120") (pintype "passive"))
    )
    (net (code "74") (name "Net-(CON1DE-S)") (class "Default")
      (node (ref "CON1") (pin "B33") (pinfunction "S_B33") (pintype "passive"))
      (node (ref "CON2") (pin "116") (pinfunction "S_116") (pintype "passive"))
    )
    (net (code "75") (name "Net-(CON1DF-S)") (class "Default")
      (node (ref "CON1") (pin "B34") (pinfunction "S_B34") (pintype "passive"))
      (node (ref "CON2") (pin "114") (pinfunction "S_114") (pintype "passive"))
    )
    (net (code "76") (name "Net-(CON1DI-S)") (class "Default")
      (node (ref "CON1") (pin "B37") (pinfunction "S_B37") (pintype "passive"))
      (node (ref "CON2") (pin "110") (pinfunction "S_110") (pintype "passive"))
    )
    (net (code "77") (name "Net-(CON1DJ-S)") (class "Default")
      (node (ref "CON1") (pin "B38") (pinfunction "S_B38") (pintype "passive"))
      (node (ref "CON2") (pin "108") (pinfunction "S_108") (pintype "passive"))
    )
    (net (code "78") (name "Net-(CON1DN-S)") (class "Default")
      (node (ref "CON1") (pin "B41") (pinfunction "S_B41") (pintype "passive"))
      (node (ref "CON2") (pin "104") (pinfunction "S_104") (pintype "passive"))
    )
    (net (code "79") (name "Net-(CON1DO-S)") (class "Default")
      (node (ref "CON1") (pin "B42") (pinfunction "S_B42") (pintype "passive"))
      (node (ref "CON2") (pin "102") (pinfunction "S_102") (pintype "passive"))
    )
    (net (code "80") (name "Net-(CON1DR-S)") (class "Default")
      (node (ref "CON1") (pin "B45") (pinfunction "S_B45") (pintype "passive"))
      (node (ref "CON2") (pin "98") (pinfunction "S_98") (pintype "passive"))
    )
    (net (code "81") (name "Net-(CON1DS-S)") (class "Default")
      (node (ref "CON1") (pin "B46") (pinfunction "S_B46") (pintype "passive"))
      (node (ref "CON2") (pin "96") (pinfunction "S_96") (pintype "passive"))
    )
    (net (code "82") (name "Net-(CON1DX-S)") (class "Default")
      (node (ref "CON1") (pin "B50") (pinfunction "S_B50") (pintype "passive"))
      (node (ref "CON2") (pin "92") (pinfunction "S_92") (pintype "passive"))
    )
    (net (code "83") (name "Net-(CON1DY-S)") (class "Default")
      (node (ref "CON1") (pin "B51") (pinfunction "S_B51") (pintype "passive"))
      (node (ref "CON2") (pin "90") (pinfunction "S_90") (pintype "passive"))
    )
    (net (code "84") (name "Net-(CON1EB-S)") (class "Default")
      (node (ref "CON1") (pin "B54") (pinfunction "S_B54") (pintype "passive"))
      (node (ref "CON2") (pin "86") (pinfunction "S_86") (pintype "passive"))
    )
    (net (code "85") (name "Net-(CON1EC-S)") (class "Default")
      (node (ref "CON1") (pin "B55") (pinfunction "S_B55") (pintype "passive"))
      (node (ref "CON2") (pin "84") (pinfunction "S_84") (pintype "passive"))
    )
    (net (code "86") (name "Net-(CON1EF-S)") (class "Default")
      (node (ref "CON1") (pin "B58") (pinfunction "S_B58") (pintype "passive"))
      (node (ref "CON2") (pin "80") (pinfunction "S_80") (pintype "passive"))
    )
    (net (code "87") (name "Net-(CON1EG-S)") (class "Default")
      (node (ref "CON1") (pin "B59") (pinfunction "S_B59") (pintype "passive"))
      (node (ref "CON2") (pin "78") (pinfunction "S_78") (pintype "passive"))
    )
    (net (code "88") (name "Net-(CON1EK-S)") (class "Default")
      (node (ref "CON1") (pin "B62") (pinfunction "S_B62") (pintype "passive"))
      (node (ref "CON2") (pin "74") (pinfunction "S_74") (pintype "passive"))
    )
    (net (code "89") (name "Net-(CON1EL-S)") (class "Default")
      (node (ref "CON1") (pin "B63") (pinfunction "S_B63") (pintype "passive"))
      (node (ref "CON2") (pin "72") (pinfunction "S_72") (pintype "passive"))
    )
    (net (code "90") (name "Net-(CON1EO-S)") (class "Default")
      (node (ref "CON1") (pin "B66") (pinfunction "S_B66") (pintype "passive"))
      (node (ref "CON2") (pin "68") (pinfunction "S_68") (pintype "passive"))
    )
    (net (code "91") (name "Net-(CON1EP-S)") (class "Default")
      (node (ref "CON1") (pin "B67") (pinfunction "S_B67") (pintype "passive"))
      (node (ref "CON2") (pin "66") (pinfunction "S_66") (pintype "passive"))
    )
    (net (code "92") (name "Net-(CON1ET-S)") (class "Default")
      (node (ref "CON1") (pin "B70") (pinfunction "S_B70") (pintype "passive"))
      (node (ref "CON2") (pin "62") (pinfunction "S_62") (pintype "passive"))
    )
    (net (code "93") (name "Net-(CON1EU-S)") (class "Default")
      (node (ref "CON1") (pin "B71") (pinfunction "S_B71") (pintype "passive"))
      (node (ref "CON2") (pin "60") (pinfunction "S_60") (pintype "passive"))
    )
    (net (code "94") (name "Net-(CON1EX-S)") (class "Default")
      (node (ref "CON1") (pin "B74") (pinfunction "S_B74") (pintype "passive"))
      (node (ref "CON2") (pin "56") (pinfunction "S_56") (pintype "passive"))
    )
    (net (code "95") (name "Net-(CON1EY-S)") (class "Default")
      (node (ref "CON1") (pin "B75") (pinfunction "S_B75") (pintype "passive"))
      (node (ref "CON2") (pin "54") (pinfunction "S_54") (pintype "passive"))
    )
    (net (code "96") (name "Net-(CON1FB-S)") (class "Default")
      (node (ref "CON1") (pin "B78") (pinfunction "S_B78") (pintype "passive"))
      (node (ref "CON2") (pin "50") (pinfunction "S_50") (pintype "passive"))
    )
    (net (code "97") (name "Net-(CON1FC-S)") (class "Default")
      (node (ref "CON1") (pin "B79") (pinfunction "S_B79") (pintype "passive"))
      (node (ref "CON2") (pin "48") (pinfunction "S_48") (pintype "passive"))
    )
    (net (code "98") (name "unconnected-(CON1A-S-PadA1)") (class "Default")
      (node (ref "CON1") (pin "A1") (pinfunction "S_A1") (pintype "passive"))
    )
    (net (code "99") (name "unconnected-(CON1AS-S-PadA5)") (class "Default")
      (node (ref "CON1") (pin "A5") (pinfunction "S_A5") (pintype "passive"))
    )
    (net (code "100") (name "unconnected-(CON1B-S-PadA10)") (class "Default")
      (node (ref "CON1") (pin "A10") (pinfunction "S_A10") (pintype "passive"))
    )
    (net (code "101") (name "unconnected-(CON1BD-S-PadA6)") (class "Default")
      (node (ref "CON1") (pin "A6") (pinfunction "S_A6") (pintype "passive"))
    )
    (net (code "102") (name "unconnected-(CON1BO-S-PadA7)") (class "Default")
      (node (ref "CON1") (pin "A7") (pinfunction "S_A7") (pintype "passive"))
    )
    (net (code "103") (name "unconnected-(CON1BZ-S-PadA8)") (class "Default")
      (node (ref "CON1") (pin "A8") (pinfunction "S_A8") (pintype "passive"))
    )
    (net (code "104") (name "unconnected-(CON1C-S-PadA11)") (class "Default")
      (node (ref "CON1") (pin "A11") (pinfunction "S_A11") (pintype "passive"))
    )
    (net (code "105") (name "unconnected-(CON1CD-S-PadA9)") (class "Default")
      (node (ref "CON1") (pin "A9") (pinfunction "S_A9") (pintype "passive"))
    )
    (net (code "106") (name "unconnected-(CON1CE-S-PadB1)") (class "Default")
      (node (ref "CON1") (pin "B1") (pinfunction "S_B1") (pintype "passive"))
    )
    (net (code "107") (name "unconnected-(CON1CF-S-PadB10)") (class "Default")
      (node (ref "CON1") (pin "B10") (pinfunction "S_B10") (pintype "passive"))
    )
    (net (code "108") (name "unconnected-(CON1CG-S-PadB11)") (class "Default")
      (node (ref "CON1") (pin "B11") (pinfunction "S_B11") (pintype "passive"))
    )
    (net (code "109") (name "unconnected-(CON1CH-S-PadB12)") (class "Default")
      (node (ref "CON1") (pin "B12") (pinfunction "S_B12") (pintype "passive"))
    )
    (net (code "110") (name "unconnected-(CON1CP-S-PadB2)") (class "Default")
      (node (ref "CON1") (pin "B2") (pinfunction "S_B2") (pintype "passive"))
    )
    (net (code "111") (name "unconnected-(CON1DA-S-PadB3)") (class "Default")
      (node (ref "CON1") (pin "B3") (pinfunction "S_B3") (pintype "passive"))
    )
    (net (code "112") (name "unconnected-(CON1DB-S-PadB30)") (class "Default")
      (node (ref "CON1") (pin "B30") (pinfunction "S_B30") (pintype "passive"))
    )
    (net (code "113") (name "unconnected-(CON1DW-S-PadB5)") (class "Default")
      (node (ref "CON1") (pin "B5") (pinfunction "S_B5") (pintype "passive"))
    )
    (net (code "114") (name "unconnected-(CON1E-S-PadA13)") (class "Default")
      (node (ref "CON1") (pin "A13") (pinfunction "S_A13") (pintype "passive"))
    )
    (net (code "115") (name "unconnected-(CON1EH-S-PadB6)") (class "Default")
      (node (ref "CON1") (pin "B6") (pinfunction "S_B6") (pintype "passive"))
    )
    (net (code "116") (name "unconnected-(CON1F-S-PadA14)") (class "Default")
      (node (ref "CON1") (pin "A14") (pinfunction "S_A14") (pintype "passive"))
    )
    (net (code "117") (name "unconnected-(CON1FD-S-PadB8)") (class "Default")
      (node (ref "CON1") (pin "B8") (pinfunction "S_B8") (pintype "passive"))
    )
    (net (code "118") (name "unconnected-(CON1FF-S-PadB81)") (class "Default")
      (node (ref "CON1") (pin "B81") (pinfunction "S_B81") (pintype "passive"))
    )
    (net (code "119") (name "unconnected-(CON1FH-S-PadB9)") (class "Default")
      (node (ref "CON1") (pin "B9") (pinfunction "S_B9") (pintype "passive"))
    )
    (net (code "120") (name "unconnected-(CON1L-S-PadA2)") (class "Default")
      (node (ref "CON1") (pin "A2") (pinfunction "S_A2") (pintype "passive"))
    )
    (net (code "121") (name "unconnected-(CON1W-S-PadA3)") (class "Default")
      (node (ref "CON1") (pin "A3") (pinfunction "S_A3") (pintype "passive"))
    )
    (net (code "122") (name "unconnected-(CON2A-S-Pad1)") (class "Default")
      (node (ref "CON2") (pin "1") (pinfunction "S_1") (pintype "passive"))
    )
    (net (code "123") (name "unconnected-(CON2AM-S-Pad14)") (class "Default")
      (node (ref "CON2") (pin "14") (pinfunction "S_14") (pintype "passive"))
    )
    (net (code "124") (name "unconnected-(CON2B-S-Pad10)") (class "Default")
      (node (ref "CON2") (pin "10") (pinfunction "S_10") (pintype "passive"))
    )
    (net (code "125") (name "unconnected-(CON2BB-S-Pad153)") (class "Default")
      (node (ref "CON2") (pin "153") (pinfunction "S_153") (pintype "passive"))
    )
    (net (code "126") (name "unconnected-(CON2BC-S-Pad154)") (class "Default")
      (node (ref "CON2") (pin "154") (pinfunction "S_154") (pintype "passive"))
    )
    (net (code "127") (name "unconnected-(CON2BD-S-Pad155)") (class "Default")
      (node (ref "CON2") (pin "155") (pinfunction "S_155") (pintype "passive"))
    )
    (net (code "128") (name "unconnected-(CON2BE-S-Pad156)") (class "Default")
      (node (ref "CON2") (pin "156") (pinfunction "S_156") (pintype "passive"))
    )
    (net (code "129") (name "unconnected-(CON2BG-S-Pad158)") (class "Default")
      (node (ref "CON2") (pin "158") (pinfunction "S_158") (pintype "passive"))
    )
    (net (code "130") (name "unconnected-(CON2BH-S-Pad159)") (class "Default")
      (node (ref "CON2") (pin "159") (pinfunction "S_159") (pintype "passive"))
    )
    (net (code "131") (name "unconnected-(CON2BI-S-Pad16)") (class "Default")
      (node (ref "CON2") (pin "16") (pinfunction "S_16") (pintype "passive"))
    )
    (net (code "132") (name "unconnected-(CON2BJ-S-Pad160)") (class "Default")
      (node (ref "CON2") (pin "160") (pinfunction "S_160") (pintype "passive"))
    )
    (net (code "133") (name "unconnected-(CON2BK-S-Pad161)") (class "Default")
      (node (ref "CON2") (pin "161") (pinfunction "S_161") (pintype "passive"))
    )
    (net (code "134") (name "unconnected-(CON2BL-S-Pad162)") (class "Default")
      (node (ref "CON2") (pin "162") (pinfunction "S_162") (pintype "passive"))
    )
    (net (code "135") (name "unconnected-(CON2BM-S-Pad163)") (class "Default")
      (node (ref "CON2") (pin "163") (pinfunction "S_163") (pintype "passive"))
    )
    (net (code "136") (name "unconnected-(CON2BN-S-Pad164)") (class "Default")
      (node (ref "CON2") (pin "164") (pinfunction "S_164") (pintype "passive"))
    )
    (net (code "137") (name "unconnected-(CON2BO-S-Pad165)") (class "Default")
      (node (ref "CON2") (pin "165") (pinfunction "S_165") (pintype "passive"))
    )
    (net (code "138") (name "unconnected-(CON2BQ-S-Pad167)") (class "Default")
      (node (ref "CON2") (pin "167") (pinfunction "S_167") (pintype "passive"))
    )
    (net (code "139") (name "unconnected-(CON2BR-S-Pad168)") (class "Default")
      (node (ref "CON2") (pin "168") (pinfunction "S_168") (pintype "passive"))
    )
    (net (code "140") (name "unconnected-(CON2BS-S-Pad169)") (class "Default")
      (node (ref "CON2") (pin "169") (pinfunction "S_169") (pintype "passive"))
    )
    (net (code "141") (name "unconnected-(CON2BU-S-Pad170)") (class "Default")
      (node (ref "CON2") (pin "170") (pinfunction "S_170") (pintype "passive"))
    )
    (net (code "142") (name "unconnected-(CON2BV-S-Pad171)") (class "Default")
      (node (ref "CON2") (pin "171") (pinfunction "S_171") (pintype "passive"))
    )
    (net (code "143") (name "unconnected-(CON2BW-S-Pad172)") (class "Default")
      (node (ref "CON2") (pin "172") (pinfunction "S_172") (pintype "passive"))
    )
    (net (code "144") (name "unconnected-(CON2BZ-S-Pad175)") (class "Default")
      (node (ref "CON2") (pin "175") (pinfunction "S_175") (pintype "passive"))
    )
    (net (code "145") (name "unconnected-(CON2CA-S-Pad176)") (class "Default")
      (node (ref "CON2") (pin "176") (pinfunction "S_176") (pintype "passive"))
    )
    (net (code "146") (name "unconnected-(CON2CB-S-Pad177)") (class "Default")
      (node (ref "CON2") (pin "177") (pinfunction "S_177") (pintype "passive"))
    )
    (net (code "147") (name "unconnected-(CON2CC-S-Pad178)") (class "Default")
      (node (ref "CON2") (pin "178") (pinfunction "S_178") (pintype "passive"))
    )
    (net (code "148") (name "unconnected-(CON2CE-S-Pad18)") (class "Default")
      (node (ref "CON2") (pin "18") (pinfunction "S_18") (pintype "passive"))
    )
    (net (code "149") (name "unconnected-(CON2CG-S-Pad181)") (class "Default")
      (node (ref "CON2") (pin "181") (pinfunction "S_181") (pintype "passive"))
    )
    (net (code "150") (name "unconnected-(CON2CH-S-Pad182)") (class "Default")
      (node (ref "CON2") (pin "182") (pinfunction "S_182") (pintype "passive"))
    )
    (net (code "151") (name "unconnected-(CON2CI-S-Pad183)") (class "Default")
      (node (ref "CON2") (pin "183") (pinfunction "S_183") (pintype "passive"))
    )
    (net (code "152") (name "unconnected-(CON2CJ-S-Pad184)") (class "Default")
      (node (ref "CON2") (pin "184") (pinfunction "S_184") (pintype "passive"))
    )
    (net (code "153") (name "unconnected-(CON2CM-S-Pad187)") (class "Default")
      (node (ref "CON2") (pin "187") (pinfunction "S_187") (pintype "passive"))
    )
    (net (code "154") (name "unconnected-(CON2CN-S-Pad188)") (class "Default")
      (node (ref "CON2") (pin "188") (pinfunction "S_188") (pintype "passive"))
    )
    (net (code "155") (name "unconnected-(CON2CO-S-Pad189)") (class "Default")
      (node (ref "CON2") (pin "189") (pinfunction "S_189") (pintype "passive"))
    )
    (net (code "156") (name "unconnected-(CON2CP-S-Pad19)") (class "Default")
      (node (ref "CON2") (pin "19") (pinfunction "S_19") (pintype "passive"))
    )
    (net (code "157") (name "unconnected-(CON2CQ-S-Pad190)") (class "Default")
      (node (ref "CON2") (pin "190") (pinfunction "S_190") (pintype "passive"))
    )
    (net (code "158") (name "unconnected-(CON2CT-S-Pad193)") (class "Default")
      (node (ref "CON2") (pin "193") (pinfunction "S_193") (pintype "passive"))
    )
    (net (code "159") (name "unconnected-(CON2CU-S-Pad194)") (class "Default")
      (node (ref "CON2") (pin "194") (pinfunction "S_194") (pintype "passive"))
    )
    (net (code "160") (name "unconnected-(CON2CV-S-Pad195)") (class "Default")
      (node (ref "CON2") (pin "195") (pinfunction "S_195") (pintype "passive"))
    )
    (net (code "161") (name "unconnected-(CON2CW-S-Pad196)") (class "Default")
      (node (ref "CON2") (pin "196") (pinfunction "S_196") (pintype "passive"))
    )
    (net (code "162") (name "unconnected-(CON2CZ-S-Pad199)") (class "Default")
      (node (ref "CON2") (pin "199") (pinfunction "S_199") (pintype "passive"))
    )
    (net (code "163") (name "unconnected-(CON2DA-S-Pad2)") (class "Default")
      (node (ref "CON2") (pin "2") (pinfunction "S_2") (pintype "passive"))
    )
    (net (code "164") (name "unconnected-(CON2DB-S-Pad20)") (class "Default")
      (node (ref "CON2") (pin "20") (pinfunction "S_20") (pintype "passive"))
    )
    (net (code "165") (name "unconnected-(CON2DC-S-Pad200)") (class "Default")
      (node (ref "CON2") (pin "200") (pinfunction "S_200") (pintype "passive"))
    )
    (net (code "166") (name "unconnected-(CON2DD-S-Pad201)") (class "Default")
      (node (ref "CON2") (pin "201") (pinfunction "S_201") (pintype "passive"))
    )
    (net (code "167") (name "unconnected-(CON2DE-S-Pad202)") (class "Default")
      (node (ref "CON2") (pin "202") (pinfunction "S_202") (pintype "passive"))
    )
    (net (code "168") (name "unconnected-(CON2DH-S-Pad205)") (class "Default")
      (node (ref "CON2") (pin "205") (pinfunction "S_205") (pintype "passive"))
    )
    (net (code "169") (name "unconnected-(CON2DI-S-Pad206)") (class "Default")
      (node (ref "CON2") (pin "206") (pinfunction "S_206") (pintype "passive"))
    )
    (net (code "170") (name "unconnected-(CON2DJ-S-Pad207)") (class "Default")
      (node (ref "CON2") (pin "207") (pinfunction "S_207") (pintype "passive"))
    )
    (net (code "171") (name "unconnected-(CON2DK-S-Pad208)") (class "Default")
      (node (ref "CON2") (pin "208") (pinfunction "S_208") (pintype "passive"))
    )
    (net (code "172") (name "unconnected-(CON2DM-S-Pad21)") (class "Default")
      (node (ref "CON2") (pin "21") (pinfunction "S_21") (pintype "passive"))
    )
    (net (code "173") (name "unconnected-(CON2DO-S-Pad211)") (class "Default")
      (node (ref "CON2") (pin "211") (pinfunction "S_211") (pintype "passive"))
    )
    (net (code "174") (name "unconnected-(CON2DP-S-Pad212)") (class "Default")
      (node (ref "CON2") (pin "212") (pinfunction "S_212") (pintype "passive"))
    )
    (net (code "175") (name "unconnected-(CON2DQ-S-Pad213)") (class "Default")
      (node (ref "CON2") (pin "213") (pinfunction "S_213") (pintype "passive"))
    )
    (net (code "176") (name "unconnected-(CON2DR-S-Pad214)") (class "Default")
      (node (ref "CON2") (pin "214") (pinfunction "S_214") (pintype "passive"))
    )
    (net (code "177") (name "unconnected-(CON2DU-S-Pad217)") (class "Default")
      (node (ref "CON2") (pin "217") (pinfunction "S_217") (pintype "passive"))
    )
    (net (code "178") (name "unconnected-(CON2DV-S-Pad218)") (class "Default")
      (node (ref "CON2") (pin "218") (pinfunction "S_218") (pintype "passive"))
    )
    (net (code "179") (name "unconnected-(CON2DW-S-Pad219)") (class "Default")
      (node (ref "CON2") (pin "219") (pinfunction "S_219") (pintype "passive"))
    )
    (net (code "180") (name "unconnected-(CON2DX-S-Pad22)") (class "Default")
      (node (ref "CON2") (pin "22") (pinfunction "S_22") (pintype "passive"))
    )
    (net (code "181") (name "unconnected-(CON2DY-S-Pad220)") (class "Default")
      (node (ref "CON2") (pin "220") (pinfunction "S_220") (pintype "passive"))
    )
    (net (code "182") (name "unconnected-(CON2EB-S-Pad223)") (class "Default")
      (node (ref "CON2") (pin "223") (pinfunction "S_223") (pintype "passive"))
    )
    (net (code "183") (name "unconnected-(CON2EC-S-Pad224)") (class "Default")
      (node (ref "CON2") (pin "224") (pinfunction "S_224") (pintype "passive"))
    )
    (net (code "184") (name "unconnected-(CON2ED-S-Pad225)") (class "Default")
      (node (ref "CON2") (pin "225") (pinfunction "S_225") (pintype "passive"))
    )
    (net (code "185") (name "unconnected-(CON2EE-S-Pad226)") (class "Default")
      (node (ref "CON2") (pin "226") (pinfunction "S_226") (pintype "passive"))
    )
    (net (code "186") (name "unconnected-(CON2EI-S-Pad23)") (class "Default")
      (node (ref "CON2") (pin "23") (pinfunction "S_23") (pintype "passive"))
    )
    (net (code "187") (name "unconnected-(CON2EJ-S-Pad230)") (class "Default")
      (node (ref "CON2") (pin "230") (pinfunction "S_230") (pintype "passive"))
    )
    (net (code "188") (name "unconnected-(CON2EL-S-Pad232)") (class "Default")
      (node (ref "CON2") (pin "232") (pinfunction "S_232") (pintype "passive"))
    )
    (net (code "189") (name "unconnected-(CON2EN-S-Pad234)") (class "Default")
      (node (ref "CON2") (pin "234") (pinfunction "S_234") (pintype "passive"))
    )
    (net (code "190") (name "unconnected-(CON2EP-S-Pad236)") (class "Default")
      (node (ref "CON2") (pin "236") (pinfunction "S_236") (pintype "passive"))
    )
    (net (code "191") (name "unconnected-(CON2ET-S-Pad24)") (class "Default")
      (node (ref "CON2") (pin "24") (pinfunction "S_24") (pintype "passive"))
    )
    (net (code "192") (name "unconnected-(CON2EU-S-Pad240)") (class "Default")
      (node (ref "CON2") (pin "240") (pinfunction "S_240") (pintype "passive"))
    )
    (net (code "193") (name "unconnected-(CON2EW-S-Pad242)") (class "Default")
      (node (ref "CON2") (pin "242") (pinfunction "S_242") (pintype "passive"))
    )
    (net (code "194") (name "unconnected-(CON2FA-S-Pad246)") (class "Default")
      (node (ref "CON2") (pin "246") (pinfunction "S_246") (pintype "passive"))
    )
    (net (code "195") (name "unconnected-(CON2FC-S-Pad248)") (class "Default")
      (node (ref "CON2") (pin "248") (pinfunction "S_248") (pintype "passive"))
    )
    (net (code "196") (name "unconnected-(CON2FE-S-Pad25)") (class "Default")
      (node (ref "CON2") (pin "25") (pinfunction "S_25") (pintype "passive"))
    )
    (net (code "197") (name "unconnected-(CON2FH-S-Pad252)") (class "Default")
      (node (ref "CON2") (pin "252") (pinfunction "S_252") (pintype "passive"))
    )
    (net (code "198") (name "unconnected-(CON2FI-S-Pad253)") (class "Default")
      (node (ref "CON2") (pin "253") (pinfunction "S_253") (pintype "passive"))
    )
    (net (code "199") (name "unconnected-(CON2FJ-S-Pad254)") (class "Default")
      (node (ref "CON2") (pin "254") (pinfunction "S_254") (pintype "passive"))
    )
    (net (code "200") (name "unconnected-(CON2FK-S-Pad255)") (class "Default")
      (node (ref "CON2") (pin "255") (pinfunction "S_255") (pintype "passive"))
    )
    (net (code "201") (name "unconnected-(CON2FN-S-Pad258)") (class "Default")
      (node (ref "CON2") (pin "258") (pinfunction "S_258") (pintype "passive"))
    )
    (net (code "202") (name "unconnected-(CON2FO-S-Pad259)") (class "Default")
      (node (ref "CON2") (pin "259") (pinfunction "S_259") (pintype "passive"))
    )
    (net (code "203") (name "unconnected-(CON2FP-S-Pad26)") (class "Default")
      (node (ref "CON2") (pin "26") (pinfunction "S_26") (pintype "passive"))
    )
    (net (code "204") (name "unconnected-(CON2FQ-S-Pad260)") (class "Default")
      (node (ref "CON2") (pin "260") (pinfunction "S_260") (pintype "passive"))
    )
    (net (code "205") (name "unconnected-(CON2FR-S-Pad261)") (class "Default")
      (node (ref "CON2") (pin "261") (pinfunction "S_261") (pintype "passive"))
    )
    (net (code "206") (name "unconnected-(CON2FU-S-Pad264)") (class "Default")
      (node (ref "CON2") (pin "264") (pinfunction "S_264") (pintype "passive"))
    )
    (net (code "207") (name "unconnected-(CON2FV-S-Pad265)") (class "Default")
      (node (ref "CON2") (pin "265") (pinfunction "S_265") (pintype "passive"))
    )
    (net (code "208") (name "unconnected-(CON2FW-S-Pad266)") (class "Default")
      (node (ref "CON2") (pin "266") (pinfunction "S_266") (pintype "passive"))
    )
    (net (code "209") (name "unconnected-(CON2FX-S-Pad267)") (class "Default")
      (node (ref "CON2") (pin "267") (pinfunction "S_267") (pintype "passive"))
    )
    (net (code "210") (name "unconnected-(CON2GA-S-Pad27)") (class "Default")
      (node (ref "CON2") (pin "27") (pinfunction "S_27") (pintype "passive"))
    )
    (net (code "211") (name "unconnected-(CON2GB-S-Pad270)") (class "Default")
      (node (ref "CON2") (pin "270") (pinfunction "S_270") (pintype "passive"))
    )
    (net (code "212") (name "unconnected-(CON2GC-S-Pad271)") (class "Default")
      (node (ref "CON2") (pin "271") (pinfunction "S_271") (pintype "passive"))
    )
    (net (code "213") (name "unconnected-(CON2GD-S-Pad272)") (class "Default")
      (node (ref "CON2") (pin "272") (pinfunction "S_272") (pintype "passive"))
    )
    (net (code "214") (name "unconnected-(CON2GE-S-Pad273)") (class "Default")
      (node (ref "CON2") (pin "273") (pinfunction "S_273") (pintype "passive"))
    )
    (net (code "215") (name "unconnected-(CON2GF-S-Pad274)") (class "Default")
      (node (ref "CON2") (pin "274") (pinfunction "S_274") (pintype "passive"))
    )
    (net (code "216") (name "unconnected-(CON2GH-S-Pad276)") (class "Default")
      (node (ref "CON2") (pin "276") (pinfunction "S_276") (pintype "passive"))
    )
    (net (code "217") (name "unconnected-(CON2GI-S-Pad277)") (class "Default")
      (node (ref "CON2") (pin "277") (pinfunction "S_277") (pintype "passive"))
    )
    (net (code "218") (name "unconnected-(CON2GJ-S-Pad278)") (class "Default")
      (node (ref "CON2") (pin "278") (pinfunction "S_278") (pintype "passive"))
    )
    (net (code "219") (name "unconnected-(CON2GK-S-Pad279)") (class "Default")
      (node (ref "CON2") (pin "279") (pinfunction "S_279") (pintype "passive"))
    )
    (net (code "220") (name "unconnected-(CON2GL-S-Pad28)") (class "Default")
      (node (ref "CON2") (pin "28") (pinfunction "S_28") (pintype "passive"))
    )
    (net (code "221") (name "unconnected-(CON2GM-S-Pad280)") (class "Default")
      (node (ref "CON2") (pin "280") (pinfunction "S_280") (pintype "passive"))
    )
    (net (code "222") (name "unconnected-(CON2GN-S-Pad281)") (class "Default")
      (node (ref "CON2") (pin "281") (pinfunction "S_281") (pintype "passive"))
    )
    (net (code "223") (name "unconnected-(CON2GO-S-Pad29)") (class "Default")
      (node (ref "CON2") (pin "29") (pinfunction "S_29") (pintype "passive"))
    )
    (net (code "224") (name "unconnected-(CON2GP-S-Pad3)") (class "Default")
      (node (ref "CON2") (pin "3") (pinfunction "S_3") (pintype "passive"))
    )
    (net (code "225") (name "unconnected-(CON2GQ-S-Pad30)") (class "Default")
      (node (ref "CON2") (pin "30") (pinfunction "S_30") (pintype "passive"))
    )
    (net (code "226") (name "unconnected-(CON2GR-S-Pad31)") (class "Default")
      (node (ref "CON2") (pin "31") (pinfunction "S_31") (pintype "passive"))
    )
    (net (code "227") (name "unconnected-(CON2GS-S-Pad32)") (class "Default")
      (node (ref "CON2") (pin "32") (pinfunction "S_32") (pintype "passive"))
    )
    (net (code "228") (name "unconnected-(CON2GT-S-Pad33)") (class "Default")
      (node (ref "CON2") (pin "33") (pinfunction "S_33") (pintype "passive"))
    )
    (net (code "229") (name "unconnected-(CON2GU-S-Pad34)") (class "Default")
      (node (ref "CON2") (pin "34") (pinfunction "S_34") (pintype "passive"))
    )
    (net (code "230") (name "unconnected-(CON2GV-S-Pad35)") (class "Default")
      (node (ref "CON2") (pin "35") (pinfunction "S_35") (pintype "passive"))
    )
    (net (code "231") (name "unconnected-(CON2GY-S-Pad38)") (class "Default")
      (node (ref "CON2") (pin "38") (pinfunction "S_38") (pintype "passive"))
    )
    (net (code "232") (name "unconnected-(CON2GZ-S-Pad39)") (class "Default")
      (node (ref "CON2") (pin "39") (pinfunction "S_39") (pintype "passive"))
    )
    (net (code "233") (name "unconnected-(CON2HA-S-Pad4)") (class "Default")
      (node (ref "CON2") (pin "4") (pinfunction "S_4") (pintype "passive"))
    )
    (net (code "234") (name "unconnected-(CON2HB-S-Pad40)") (class "Default")
      (node (ref "CON2") (pin "40") (pinfunction "S_40") (pintype "passive"))
    )
    (net (code "235") (name "unconnected-(CON2HC-S-Pad41)") (class "Default")
      (node (ref "CON2") (pin "41") (pinfunction "S_41") (pintype "passive"))
    )
    (net (code "236") (name "unconnected-(CON2HD-S-Pad42)") (class "Default")
      (node (ref "CON2") (pin "42") (pinfunction "S_42") (pintype "passive"))
    )
    (net (code "237") (name "unconnected-(CON2HE-S-Pad43)") (class "Default")
      (node (ref "CON2") (pin "43") (pinfunction "S_43") (pintype "passive"))
    )
    (net (code "238") (name "unconnected-(CON2HF-S-Pad44)") (class "Default")
      (node (ref "CON2") (pin "44") (pinfunction "S_44") (pintype "passive"))
    )
    (net (code "239") (name "unconnected-(CON2HG-S-Pad45)") (class "Default")
      (node (ref "CON2") (pin "45") (pinfunction "S_45") (pintype "passive"))
    )
    (net (code "240") (name "unconnected-(CON2HL-S-Pad5)") (class "Default")
      (node (ref "CON2") (pin "5") (pinfunction "S_5") (pintype "passive"))
    )
    (net (code "241") (name "unconnected-(CON2HW-S-Pad6)") (class "Default")
      (node (ref "CON2") (pin "6") (pinfunction "S_6") (pintype "passive"))
    )
    (net (code "242") (name "unconnected-(CON2IH-S-Pad7)") (class "Default")
      (node (ref "CON2") (pin "7") (pinfunction "S_7") (pintype "passive"))
    )
    (net (code "243") (name "unconnected-(CON2IS-S-Pad8)") (class "Default")
      (node (ref "CON2") (pin "8") (pinfunction "S_8") (pintype "passive"))
    )
    (net (code "244") (name "unconnected-(CON2JD-S-Pad9)") (class "Default")
      (node (ref "CON2") (pin "9") (pinfunction "S_9") (pintype "passive"))
    )
    (net (code "245") (name "unconnected-(CON2JO-S-PadE1)") (class "Default")
      (node (ref "CON2") (pin "E1") (pinfunction "S_E1") (pintype "passive"))
    )
    (net (code "246") (name "unconnected-(CON2JP-S-PadE2)") (class "Default")
      (node (ref "CON2") (pin "E2") (pinfunction "S_E2") (pintype "passive"))
    )
  )
)
